# BG95_Misc.net
KiCad netlist of a schematic drawn in Altium Designer
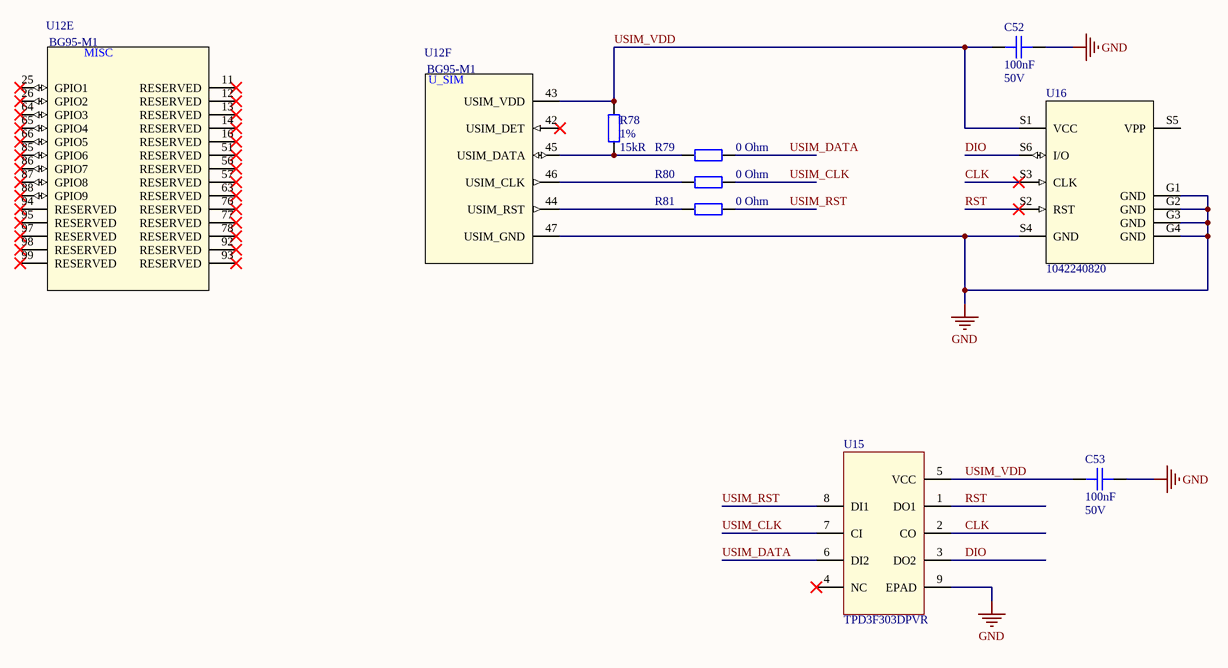
[diagram p0: BG95_Misc.SchDoc]

(export (version "E")
  (design (tool "Eeschema 10.0.6"))
  (components
    (comp (ref "C52")
      (value "CAP CER 0.1UF 50V X7R 0402")
      (footprint "C0402")
      (description "0.1µF ±10% 50V Ceramic Capacitor X7R 0402 (1005 Metric)")
      (fields
        (field (name "MANUFACTURER") "TDK")
        (field (name "MANUFACTURER PART NUMBER") "CGA2B3X7R1H104K050BB")
        (field (name "CAPACITANCE") "100nF")
        (field (name "VOLTAGE") "50V")
      )
      (libsource (lib "capacitors_smd") (part "CAP CER 0.1UF 50V X7R 0402"))
    )
    (comp (ref "C53")
      (value "CAP CER 0.1UF 50V X7R 0402")
      (footprint "C0402")
      (description "0.1µF ±10% 50V Ceramic Capacitor X7R 0402 (1005 Metric)")
      (fields
        (field (name "MANUFACTURER") "TDK")
        (field (name "MANUFACTURER PART NUMBER") "CGA2B3X7R1H104K050BB")
        (field (name "CAPACITANCE") "100nF")
        (field (name "VOLTAGE") "50V")
      )
      (libsource (lib "capacitors_smd") (part "CAP CER 0.1UF 50V X7R 0402"))
    )
    (comp (ref "R78")
      (value "RES SMD 15K OHM 1% 1/16W 0402")
      (footprint "R0402")
      (description "15 kOhms ±1% 0.063W, 1/16W Chip Resistor 0402 (1005 Metric)  Thick Film")
      (fields
        (field (name "MANUFACTURER") "Yageo")
        (field (name "MANUFACTURER PART NUMBER") "RC0402FR-0715KL")
        (field (name "TOLERANCE") "1%")
        (field (name "RESISTANCE") "15kR")
      )
      (libsource (lib "resistors_smd") (part "RES SMD 15K OHM 1% 1/16W 0402"))
    )
    (comp (ref "R79")
      (value "RES SMD 0 OHM JUMPER 1/16W 0402")
      (footprint "R0402")
      (description "0 Ohms Jumper 0.063W, 1/16W Chip Resistor 0402 (1005 Metric) Moisture Resistant Thick Film")
      (fields
        (field (name "MANUFACTURER") "Yageo")
        (field (name "MANUFACTURER PART NUMBER") "RC0402JR-070RL")
        (field (name "RESISTANCE") "0 Ohm")
      )
      (libsource (lib "resistors_smd") (part "RES SMD 0 OHM JUMPER 1/16W 0402"))
    )
    (comp (ref "R80")
      (value "RES SMD 0 OHM JUMPER 1/16W 0402")
      (footprint "R0402")
      (description "0 Ohms Jumper 0.063W, 1/16W Chip Resistor 0402 (1005 Metric) Moisture Resistant Thick Film")
      (fields
        (field (name "MANUFACTURER") "Yageo")
        (field (name "MANUFACTURER PART NUMBER") "RC0402JR-070RL")
        (field (name "RESISTANCE") "0 Ohm")
      )
      (libsource (lib "resistors_smd") (part "RES SMD 0 OHM JUMPER 1/16W 0402"))
    )
    (comp (ref "R81")
      (value "RES SMD 0 OHM JUMPER 1/16W 0402")
      (footprint "R0402")
      (description "0 Ohms Jumper 0.063W, 1/16W Chip Resistor 0402 (1005 Metric) Moisture Resistant Thick Film")
      (fields
        (field (name "MANUFACTURER") "Yageo")
        (field (name "MANUFACTURER PART NUMBER") "RC0402JR-070RL")
        (field (name "RESISTANCE") "0 Ohm")
      )
      (libsource (lib "resistors_smd") (part "RES SMD 0 OHM JUMPER 1/16W 0402"))
    )
    (comp (ref "U12")
      (value "BG95-M1")
      (footprint "BG95")
      (description "LTE Cat M1, LTE Cat NB2 and EGPRS Transceiver Module Antenna Not Included Surface Mount")
      (fields (field (name "MANUFACTURER") "QUECTEL"))
      (libsource (lib "BLDC_Motor_Driver") (part "MOD BG95 RX TXRX CELLULAR LTE/NAV SMD"))
    )
    (comp (ref "U15")
      (value "TPD3F303DPVR")
      (footprint "DPV8_1P7X0P4")
      (description "RC (Pi) EMI Filter 2nd Order Low Pass 3 Channel R = 47Ohms, 100Ohms, C = 20pF  8-UFDFN Exposed Pad")
      (fields (field (name "MANUFACTURER") "Texas Instruments"))
      (libsource (lib "diodes_tvs") (part "FILTER RC(PI) ESD SMD  8-UFDFN EP"))
    )
    (comp (ref "U16")
      (value "1042240820")
      (footprint "1042240820_MOL")
      (description "6 Position Card Connector NANO SIM Surface Mount, Right Angle Gold")
      (fields (field (name "MANUFACTURER") "Molex"))
      (libsource (lib "connectors_slots") (part "NANOSIM SOCKET 1.11H P/PULL TYPE"))
    )
  )
  (nets
    (net (code "1") (name "/CLK") (class "Default")
      (node (ref "U15") (pin "2") (pinfunction "CO_2") (pintype "passive"))
      (node (ref "U16") (pin "S3") (pinfunction "CLK_S3") (pintype "input"))
    )
    (net (code "2") (name "/DIO") (class "Default")
      (node (ref "U15") (pin "3") (pinfunction "DO2_3") (pintype "passive"))
      (node (ref "U16") (pin "S6") (pinfunction "I/O_S6") (pintype "bidirectional"))
    )
    (net (code "3") (name "/RST") (class "Default")
      (node (ref "U15") (pin "1") (pinfunction "DO1_1") (pintype "passive"))
      (node (ref "U16") (pin "S2") (pinfunction "RST_S2") (pintype "input"))
    )
    (net (code "4") (name "/USIM_CLK") (class "Default")
      (node (ref "R80") (pin "2") (pinfunction "2_2") (pintype "passive"))
      (node (ref "U15") (pin "7") (pinfunction "CI_7") (pintype "passive"))
    )
    (net (code "5") (name "/USIM_DATA") (class "Default")
      (node (ref "R79") (pin "2") (pinfunction "2_2") (pintype "passive"))
      (node (ref "U15") (pin "6") (pinfunction "DI2_6") (pintype "passive"))
    )
    (net (code "6") (name "/USIM_RST") (class "Default")
      (node (ref "R81") (pin "2") (pinfunction "2_2") (pintype "passive"))
      (node (ref "U15") (pin "8") (pinfunction "DI1_8") (pintype "passive"))
    )
    (net (code "7") (name "/USIM_VDD") (class "Default")
      (node (ref "C52") (pin "1") (pinfunction "1_1") (pintype "passive"))
      (node (ref "C53") (pin "1") (pinfunction "1_1") (pintype "passive"))
      (node (ref "R78") (pin "2") (pinfunction "2_2") (pintype "passive"))
      (node (ref "U12") (pin "43") (pinfunction "USIM_VDD_43") (pintype "power_in"))
      (node (ref "U15") (pin "5") (pinfunction "VCC_5") (pintype "power_in"))
      (node (ref "U16") (pin "S1") (pinfunction "VCC_S1") (pintype "power_in"))
    )
    (net (code "8") (name "GND") (class "Default")
      (node (ref "C52") (pin "2") (pinfunction "2_2") (pintype "passive"))
      (node (ref "C53") (pin "2") (pinfunction "2_2") (pintype "passive"))
      (node (ref "U12") (pin "47") (pinfunction "USIM_GND_47") (pintype "power_in"))
      (node (ref "U15") (pin "9") (pinfunction "EPAD_9") (pintype "passive"))
      (node (ref "U16") (pin "G1") (pinfunction "GND_G1") (pintype "power_in"))
      (node (ref "U16") (pin "G2") (pinfunction "GND_G2") (pintype "power_in"))
      (node (ref "U16") (pin "G3") (pinfunction "GND_G3") (pintype "power_in"))
      (node (ref "U16") (pin "G4") (pinfunction "GND_G4") (pintype "power_in"))
      (node (ref "U16") (pin "S4") (pinfunction "GND_S4") (pintype "power_in"))
    )
    (net (code "9") (name "Net-(U12F-USIM_CLK)") (class "Default")
      (node (ref "R80") (pin "1") (pinfunction "1_1") (pintype "passive"))
      (node (ref "U12") (pin "46") (pinfunction "USIM_CLK_46") (pintype "output"))
    )
    (net (code "10") (name "Net-(U12F-USIM_DATA)") (class "Default")
      (node (ref "R78") (pin "1") (pinfunction "1_1") (pintype "passive"))
      (node (ref "R79") (pin "1") (pinfunction "1_1") (pintype "passive"))
      (node (ref "U12") (pin "45") (pinfunction "USIM_DATA_45") (pintype "bidirectional"))
    )
    (net (code "11") (name "Net-(U12F-USIM_RST)") (class "Default")
      (node (ref "R81") (pin "1") (pinfunction "1_1") (pintype "passive"))
      (node (ref "U12") (pin "44") (pinfunction "USIM_RST_44") (pintype "output"))
    )
    (net (code "12") (name "unconnected-(U12E-GPIO1-Pad25)") (class "Default")
      (node (ref "U12") (pin "25") (pinfunction "GPIO1_25") (pintype "bidirectional+no_connect"))
    )
    (net (code "13") (name "unconnected-(U12E-GPIO2-Pad26)") (class "Default")
      (node (ref "U12") (pin "26") (pinfunction "GPIO2_26") (pintype "bidirectional+no_connect"))
    )
    (net (code "14") (name "unconnected-(U12E-GPIO3-Pad64)") (class "Default")
      (node (ref "U12") (pin "64") (pinfunction "GPIO3_64") (pintype "bidirectional+no_connect"))
    )
    (net (code "15") (name "unconnected-(U12E-GPIO4-Pad65)") (class "Default")
      (node (ref "U12") (pin "65") (pinfunction "GPIO4_65") (pintype "bidirectional+no_connect"))
    )
    (net (code "16") (name "unconnected-(U12E-GPIO5-Pad66)") (class "Default")
      (node (ref "U12") (pin "66") (pinfunction "GPIO5_66") (pintype "bidirectional+no_connect"))
    )
    (net (code "17") (name "unconnected-(U12E-GPIO6-Pad85)") (class "Default")
      (node (ref "U12") (pin "85") (pinfunction "GPIO6_85") (pintype "bidirectional+no_connect"))
    )
    (net (code "18") (name "unconnected-(U12E-GPIO7-Pad86)") (class "Default")
      (node (ref "U12") (pin "86") (pinfunction "GPIO7_86") (pintype "bidirectional+no_connect"))
    )
    (net (code "19") (name "unconnected-(U12E-GPIO8-Pad87)") (class "Default")
      (node (ref "U12") (pin "87") (pinfunction "GPIO8_87") (pintype "bidirectional+no_connect"))
    )
    (net (code "20") (name "unconnected-(U12E-GPIO9-Pad88)") (class "Default")
      (node (ref "U12") (pin "88") (pinfunction "GPIO9_88") (pintype "bidirectional+no_connect"))
    )
    (net (code "21") (name "unconnected-(U12E-RESERVED-Pad11)") (class "Default")
      (node (ref "U12") (pin "11") (pinfunction "RESERVED_11") (pintype "passive+no_connect"))
    )
    (net (code "22") (name "unconnected-(U12E-RESERVED-Pad12)") (class "Default")
      (node (ref "U12") (pin "12") (pinfunction "RESERVED_12") (pintype "passive+no_connect"))
    )
    (net (code "23") (name "unconnected-(U12E-RESERVED-Pad13)") (class "Default")
      (node (ref "U12") (pin "13") (pinfunction "RESERVED_13") (pintype "passive+no_connect"))
    )
    (net (code "24") (name "unconnected-(U12E-RESERVED-Pad14)") (class "Default")
      (node (ref "U12") (pin "14") (pinfunction "RESERVED_14") (pintype "passive+no_connect"))
    )
    (net (code "25") (name "unconnected-(U12E-RESERVED-Pad16)") (class "Default")
      (node (ref "U12") (pin "16") (pinfunction "RESERVED_16") (pintype "passive+no_connect"))
    )
    (net (code "26") (name "unconnected-(U12E-RESERVED-Pad51)") (class "Default")
      (node (ref "U12") (pin "51") (pinfunction "RESERVED_51") (pintype "passive+no_connect"))
    )
    (net (code "27") (name "unconnected-(U12E-RESERVED-Pad56)") (class "Default")
      (node (ref "U12") (pin "56") (pinfunction "RESERVED_56") (pintype "passive+no_connect"))
    )
    (net (code "28") (name "unconnected-(U12E-RESERVED-Pad57)") (class "Default")
      (node (ref "U12") (pin "57") (pinfunction "RESERVED_57") (pintype "passive+no_connect"))
    )
    (net (code "29") (name "unconnected-(U12E-RESERVED-Pad63)") (class "Default")
      (node (ref "U12") (pin "63") (pinfunction "RESERVED_63") (pintype "passive+no_connect"))
    )
    (net (code "30") (name "unconnected-(U12E-RESERVED-Pad76)") (class "Default")
      (node (ref "U12") (pin "76") (pinfunction "RESERVED_76") (pintype "passive+no_connect"))
    )
    (net (code "31") (name "unconnected-(U12E-RESERVED-Pad77)") (class "Default")
      (node (ref "U12") (pin "77") (pinfunction "RESERVED_77") (pintype "passive+no_connect"))
    )
    (net (code "32") (name "unconnected-(U12E-RESERVED-Pad78)") (class "Default")
      (node (ref "U12") (pin "78") (pinfunction "RESERVED_78") (pintype "passive+no_connect"))
    )
    (net (code "33") (name "unconnected-(U12E-RESERVED-Pad92)") (class "Default")
      (node (ref "U12") (pin "92") (pinfunction "RESERVED_92") (pintype "passive+no_connect"))
    )
    (net (code "34") (name "unconnected-(U12E-RESERVED-Pad93)") (class "Default")
      (node (ref "U12") (pin "93") (pinfunction "RESERVED_93") (pintype "passive+no_connect"))
    )
    (net (code "35") (name "unconnected-(U12E-RESERVED-Pad94)") (class "Default")
      (node (ref "U12") (pin "94") (pinfunction "RESERVED_94") (pintype "passive+no_connect"))
    )
    (net (code "36") (name "unconnected-(U12E-RESERVED-Pad95)") (class "Default")
      (node (ref "U12") (pin "95") (pinfunction "RESERVED_95") (pintype "passive+no_connect"))
    )
    (net (code "37") (name "unconnected-(U12E-RESERVED-Pad97)") (class "Default")
      (node (ref "U12") (pin "97") (pinfunction "RESERVED_97") (pintype "passive+no_connect"))
    )
    (net (code "38") (name "unconnected-(U12E-RESERVED-Pad98)") (class "Default")
      (node (ref "U12") (pin "98") (pinfunction "RESERVED_98") (pintype "passive+no_connect"))
    )
    (net (code "39") (name "unconnected-(U12E-RESERVED-Pad99)") (class "Default")
      (node (ref "U12") (pin "99") (pinfunction "RESERVED_99") (pintype "passive+no_connect"))
    )
    (net (code "40") (name "unconnected-(U12F-USIM_DET-Pad42)") (class "Default")
      (node (ref "U12") (pin "42") (pinfunction "USIM_DET_42") (pintype "input+no_connect"))
    )
    (net (code "41") (name "unconnected-(U15-NC-Pad4)") (class "Default")
      (node (ref "U15") (pin "4") (pinfunction "NC_4") (pintype "passive+no_connect"))
    )
    (net (code "42") (name "unconnected-(U16-VPP-PadS5)") (class "Default")
      (node (ref "U16") (pin "S5") (pinfunction "VPP_S5") (pintype "power_in"))
    )
  )
)
